# power_supply_blk.net
KiCad netlist of a schematic drawn in Altium Designer
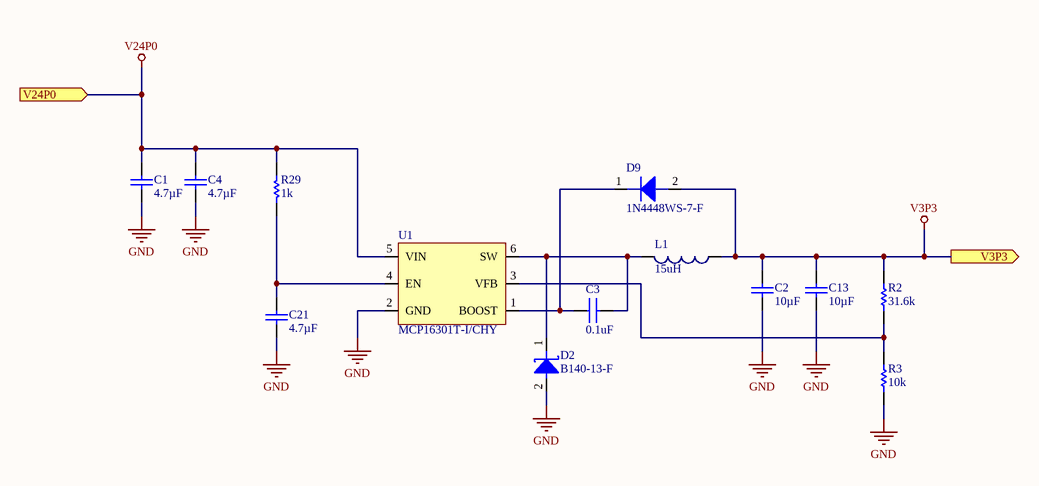
[diagram p0: power_supply_blk.SchDoc]

(export (version "E")
  (design (tool "Eeschema 10.0.6"))
  (components
    (comp (ref "C1")
      (value "4.7µF")
      (footprint "C1210")
      (description "CAP CER 4.7UF 50V X7R 1210")
      (fields (field (name "MPN") "UMK325B7475KM-T"))
      (libsource (lib "Capacitor") (part "UMK325B7475KM-T"))
    )
    (comp (ref "C2")
      (value "10µF")
      (footprint "C0805")
      (description "CAP CER 10UF 6.3V X7R 0805")
      (fields (field (name "MPN") "JMK212B7106KG-T"))
      (libsource (lib "Capacitor") (part "JMK212B7106KG-T"))
    )
    (comp (ref "C3")
      (value "0.1uF")
      (footprint "C0603")
      (description "CAP CER 0.1UF 25V X7R 0603")
      (fields (field (name "MPN") "06033C104JAT2A"))
      (libsource (lib "Capacitor") (part "06033C104JAT2A"))
    )
    (comp (ref "C4")
      (value "4.7µF")
      (footprint "C1210")
      (description "CAP CER 4.7UF 50V X7R 1210")
      (fields (field (name "MPN") "UMK325B7475KM-T"))
      (libsource (lib "Capacitor") (part "UMK325B7475KM-T"))
    )
    (comp (ref "C13")
      (value "10µF")
      (footprint "C0805")
      (description "CAP CER 10UF 6.3V X7R 0805")
      (fields (field (name "MPN") "JMK212B7106KG-T"))
      (libsource (lib "Capacitor") (part "JMK212B7106KG-T"))
    )
    (comp (ref "C21")
      (value "4.7µF")
      (footprint "C1210")
      (description "CAP CER 4.7UF 50V X7R 1210")
      (fields (field (name "MPN") "UMK325B7475KM-T"))
      (libsource (lib "Capacitor") (part "UMK325B7475KM-T"))
    )
    (comp (ref "D2")
      (value "B140-13-F")
      (footprint "DO-214AC, SMA")
      (description "DIODE SCHOTTKY 40V 1A SMA")
      (libsource (lib "Diode") (part "B140-13-F"))
    )
    (comp (ref "D9")
      (value "1N4448WS-7-F")
      (footprint "SOD-323")
      (description "DIODE GEN PURP 75V 250MA SOD323")
      (libsource (lib "Diode") (part "1N4448WS-7-F"))
    )
    (comp (ref "L1")
      (value "15uH")
      (footprint "MSS6132-153MLC")
      (description "Fixed Inductors MSS6132 AEC-Q200 15 uH 20 % 2.2 A")
      (fields (field (name "MPN") "MSS6132-153MLC"))
      (libsource (lib "Inductor") (part "MSS6132-153MLC"))
    )
    (comp (ref "R2")
      (value "31.6k")
      (footprint "R0603")
      (description "RES SMD 31.6K OHM 1% 1/10W 0603")
      (fields (field (name "MPN") "ERJ-3EKF3162V"))
      (libsource (lib "Res") (part "ERJ-3EKF3162V"))
    )
    (comp (ref "R3")
      (value "10k")
      (footprint "R0603")
      (description "RES SMD 10K OHM 1% 1/10W 0603")
      (fields (field (name "MPN") "ERJ-3EKF1002V"))
      (libsource (lib "Res") (part "ERJ-3EKF1002V"))
    )
    (comp (ref "R29")
      (value "1k")
      (footprint "R1206")
      (description "RES 1K OHM 1% 1/2W 1206")
      (fields (field (name "MPN") "RNCP1206FTD1K00"))
      (libsource (lib "Res") (part "RNCP1206FTD1K00"))
    )
    (comp (ref "U1")
      (value "MCP16301T-I/CHY")
      (footprint "SOT-23-6")
      (description "IC REG BUCK ADJ 0.6A SOT23-6")
      (libsource (lib "IC") (part "MCP16301T-I/CHY"))
    )
  )
  (nets
    (net (code "1") (name "GND") (class "Default")
      (node (ref "C1") (pin "2") (pinfunction "2_2") (pintype "passive"))
      (node (ref "C13") (pin "2") (pinfunction "2_2") (pintype "passive"))
      (node (ref "C2") (pin "2") (pinfunction "2_2") (pintype "passive"))
      (node (ref "C21") (pin "2") (pinfunction "2_2") (pintype "passive"))
      (node (ref "C4") (pin "2") (pinfunction "2_2") (pintype "passive"))
      (node (ref "D2") (pin "2") (pinfunction "anode_2") (pintype "passive"))
      (node (ref "R3") (pin "1") (pinfunction "1_1") (pintype "passive"))
      (node (ref "U1") (pin "2") (pinfunction "GND_2") (pintype "passive"))
    )
    (net (code "2") (name "Net-(D2-cathode)") (class "Default")
      (node (ref "C3") (pin "2") (pinfunction "2_2") (pintype "passive"))
      (node (ref "D2") (pin "1") (pinfunction "cathode_1") (pintype "passive"))
      (node (ref "L1") (pin "1") (pinfunction "1_1") (pintype "passive"))
      (node (ref "U1") (pin "6") (pinfunction "SW_6") (pintype "passive"))
    )
    (net (code "3") (name "Net-(D9-CATHODE)") (class "Default")
      (node (ref "C3") (pin "1") (pinfunction "1_1") (pintype "passive"))
      (node (ref "D9") (pin "1") (pinfunction "CATHODE_1") (pintype "passive"))
      (node (ref "U1") (pin "1") (pinfunction "BOOST_1") (pintype "passive"))
    )
    (net (code "4") (name "Net-(U1-EN)") (class "Default")
      (node (ref "C21") (pin "1") (pinfunction "1_1") (pintype "passive"))
      (node (ref "R29") (pin "1") (pinfunction "1_1") (pintype "passive"))
      (node (ref "U1") (pin "4") (pinfunction "EN_4") (pintype "passive"))
    )
    (net (code "5") (name "Net-(U1-VFB)") (class "Default")
      (node (ref "R2") (pin "1") (pinfunction "1_1") (pintype "passive"))
      (node (ref "R3") (pin "2") (pinfunction "2_2") (pintype "passive"))
      (node (ref "U1") (pin "3") (pinfunction "VFB_3") (pintype "passive"))
    )
    (net (code "6") (name "V3P3") (class "Default")
      (node (ref "C13") (pin "1") (pinfunction "1_1") (pintype "passive"))
      (node (ref "C2") (pin "1") (pinfunction "1_1") (pintype "passive"))
      (node (ref "D9") (pin "2") (pinfunction "ANODE_2") (pintype "passive"))
      (node (ref "L1") (pin "2") (pinfunction "2_2") (pintype "passive"))
      (node (ref "R2") (pin "2") (pinfunction "2_2") (pintype "passive"))
    )
    (net (code "7") (name "V24P0") (class "Default")
      (node (ref "C1") (pin "1") (pinfunction "1_1") (pintype "passive"))
      (node (ref "C4") (pin "1") (pinfunction "1_1") (pintype "passive"))
      (node (ref "R29") (pin "2") (pinfunction "2_2") (pintype "passive"))
      (node (ref "U1") (pin "5") (pinfunction "VIN_5") (pintype "passive"))
    )
  )
)
